# MJE13001_SMPS_5V_1A.net
KiCad netlist of a schematic drawn in Altium Designer
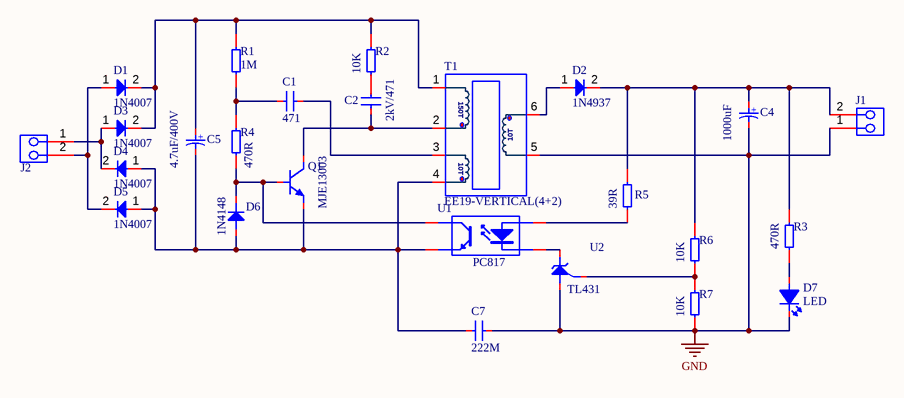
[diagram p0: MJE13001_SMPS_5V_1A.SchDoc]

(export (version "E")
  (design (tool "Eeschema 10.0.6"))
  (components
    (comp (ref "C1")
      (value "471")
      (footprint "CAP_DISC_104")
      (libsource (lib "MyAltiumLibrary") (part "Capacitors(Disc)"))
    )
    (comp (ref "C2")
      (value "2kV/471")
      (footprint "CAP_DISC_Y1222")
      (libsource (lib "MyAltiumLibrary") (part "Capacitors(Disc)"))
    )
    (comp (ref "C4")
      (value "1000uF")
      (footprint "CAP_RAD_D8x11.5_POL_BK")
      (libsource (lib "MyAltiumLibrary") (part "Capacitor(Radian)"))
    )
    (comp (ref "C5")
      (value "4.7uF/400V")
      (footprint "CAP_RAD_D8x11.5_POL_BK")
      (libsource (lib "MyAltiumLibrary") (part "Capacitor(Radian)"))
    )
    (comp (ref "C7")
      (value "222M")
      (footprint "CAP_DISC_Y2222")
      (libsource (lib "MyAltiumLibrary") (part "Capacitors(Disc)"))
    )
    (comp (ref "D1")
      (value "1N4007")
      (footprint "DO-41")
      (libsource (lib "MyAltiumLibrary") (part "Diode-1N4007"))
    )
    (comp (ref "D2")
      (value "1N4937")
      (footprint "DO-41")
      (libsource (lib "MyAltiumLibrary") (part "Diode-1N4937"))
    )
    (comp (ref "D3")
      (value "1N4007")
      (footprint "DO-41")
      (libsource (lib "MyAltiumLibrary") (part "Diode-1N4007"))
    )
    (comp (ref "D4")
      (value "1N4007")
      (footprint "DO-41")
      (libsource (lib "MyAltiumLibrary") (part "Diode-1N4007"))
    )
    (comp (ref "D5")
      (value "1N4007")
      (footprint "DO-41")
      (libsource (lib "MyAltiumLibrary") (part "Diode-1N4007"))
    )
    (comp (ref "D6")
      (value "1N4148")
      (footprint "DO-35 Horizontal")
      (libsource (lib "MyAltiumLibrary") (part "Diode-1N4148"))
    )
    (comp (ref "D7")
      (value "LED")
      (footprint "LED_3MM_GREEN")
      (libsource (lib "MyAltiumLibrary") (part "LED 3MM"))
    )
    (comp (ref "J1")
      (value "DEGSON Screws")
      (footprint "DG127-5.0-02P-14-00AH")
      (libsource (lib "") (part "DG127-5.0-02P-14-00AH_1"))
    )
    (comp (ref "J2")
      (value "DEGSON Screws")
      (footprint "DG127-5.0-02P-14-00AH")
      (libsource (lib "MyAltiumLibrary") (part "DG127-5.0-02P-14-00AH"))
    )
    (comp (ref "Q1")
      (value "MJE13003")
      (footprint "TO-126")
      (libsource (lib "MyAltiumLibrary") (part "Transistor-MJE13003"))
    )
    (comp (ref "R1")
      (value "1M")
      (footprint "RES-0.25W-H-MF")
      (libsource (lib "MyAltiumLibrary") (part "Resistors THD"))
    )
    (comp (ref "R2")
      (value "10K")
      (footprint "RES-0.25W-H-MF")
      (libsource (lib "MyAltiumLibrary") (part "Resistors THD"))
    )
    (comp (ref "R3")
      (value "470R")
      (footprint "RES-0.25W-H-MF")
      (libsource (lib "MyAltiumLibrary") (part "Resistors THD"))
    )
    (comp (ref "R4")
      (value "470R")
      (footprint "RES-0.25W-H-MF")
      (libsource (lib "MyAltiumLibrary") (part "Resistors THD"))
    )
    (comp (ref "R5")
      (value "39R")
      (footprint "RES-0.25W-H-MF")
      (libsource (lib "MyAltiumLibrary") (part "Resistors THD"))
    )
    (comp (ref "R6")
      (value "10K")
      (footprint "RES-0.25W-H-MF")
      (libsource (lib "MyAltiumLibrary") (part "Resistors THD"))
    )
    (comp (ref "R7")
      (value "10K")
      (footprint "RES-0.25W-H-MF")
      (libsource (lib "MyAltiumLibrary") (part "Resistors THD"))
    )
    (comp (ref "T1")
      (value "EE19-VERTICAL(4+2)")
      (footprint "TRANSFORMER-EE19(4+2)")
      (libsource (lib "MyAltiumLibrary") (part "TRANS-EE19-VERTICAL(4+2)"))
    )
    (comp (ref "U1")
      (value "PC817")
      (footprint "PC817-DIP")
      (libsource (lib "MyAltiumLibrary") (part "Opto-PC817"))
    )
    (comp (ref "U2")
      (value "TL431")
      (footprint "TO-92")
      (libsource (lib "MyAltiumLibrary") (part "Ic-TL431"))
    )
  )
  (nets
    (net (code "1") (name "GND") (class "Default")
      (node (ref "C4") (pin "2") (pinfunction "2_2") (pintype "passive"))
      (node (ref "C7") (pin "2") (pinfunction "2_2") (pintype "passive"))
      (node (ref "D7") (pin "2") (pinfunction "K_2") (pintype "passive"))
      (node (ref "J1") (pin "1") (pinfunction "1_1") (pintype "passive"))
      (node (ref "R7") (pin "1") (pinfunction "1_1") (pintype "passive"))
      (node (ref "T1") (pin "5") (pinfunction "5_5") (pintype "passive"))
      (node (ref "U2") (pin "2") (pinfunction "2_2") (pintype "passive"))
    )
    (net (code "2") (name "Net-(C1-Pad1)") (class "Default")
      (node (ref "C1") (pin "1") (pinfunction "1_1") (pintype "passive"))
      (node (ref "R1") (pin "1") (pinfunction "1_1") (pintype "passive"))
      (node (ref "R4") (pin "2") (pinfunction "2_2") (pintype "passive"))
    )
    (net (code "3") (name "Net-(C1-Pad2)") (class "Default")
      (node (ref "C1") (pin "2") (pinfunction "2_2") (pintype "passive"))
      (node (ref "T1") (pin "3") (pinfunction "1_3") (pintype "passive"))
    )
    (net (code "4") (name "Net-(C2-Pad2)") (class "Default")
      (node (ref "C2") (pin "2") (pinfunction "2_2") (pintype "passive"))
      (node (ref "R2") (pin "1") (pinfunction "1_1") (pintype "passive"))
    )
    (net (code "5") (name "Net-(C4-Pad1)") (class "Default")
      (node (ref "C4") (pin "1") (pinfunction "1_1") (pintype "passive"))
      (node (ref "D2") (pin "2") (pinfunction "2_2") (pintype "passive"))
      (node (ref "J1") (pin "2") (pinfunction "2_2") (pintype "passive"))
      (node (ref "R3") (pin "2") (pinfunction "2_2") (pintype "passive"))
      (node (ref "R5") (pin "2") (pinfunction "2_2") (pintype "passive"))
      (node (ref "R6") (pin "2") (pinfunction "2_2") (pintype "passive"))
    )
    (net (code "6") (name "Net-(C5-Pad1)") (class "Default")
      (node (ref "C5") (pin "1") (pinfunction "1_1") (pintype "passive"))
      (node (ref "D1") (pin "2") (pinfunction "2_2") (pintype "passive"))
      (node (ref "D3") (pin "2") (pinfunction "2_2") (pintype "passive"))
      (node (ref "R1") (pin "2") (pinfunction "2_2") (pintype "passive"))
      (node (ref "R2") (pin "2") (pinfunction "2_2") (pintype "passive"))
      (node (ref "T1") (pin "1") (pinfunction "1_1") (pintype "passive"))
    )
    (net (code "7") (name "Net-(D1-Pad1)") (class "Default")
      (node (ref "D1") (pin "1") (pinfunction "1_1") (pintype "passive"))
      (node (ref "D5") (pin "2") (pinfunction "2_2") (pintype "passive"))
      (node (ref "J2") (pin "2") (pinfunction "2_2") (pintype "passive"))
    )
    (net (code "8") (name "Net-(D2-Pad1)") (class "Default")
      (node (ref "D2") (pin "1") (pinfunction "1_1") (pintype "passive"))
      (node (ref "T1") (pin "6") (pinfunction "6_6") (pintype "passive"))
    )
    (net (code "9") (name "Net-(D3-Pad1)") (class "Default")
      (node (ref "D3") (pin "1") (pinfunction "1_1") (pintype "passive"))
      (node (ref "D4") (pin "2") (pinfunction "2_2") (pintype "passive"))
      (node (ref "J2") (pin "1") (pinfunction "1_1") (pintype "passive"))
    )
    (net (code "10") (name "Net-(D7-A)") (class "Default")
      (node (ref "D7") (pin "1") (pinfunction "A_1") (pintype "passive"))
      (node (ref "R3") (pin "1") (pinfunction "1_1") (pintype "passive"))
    )
    (net (code "11") (name "Net-(Q1-B)") (class "Default")
      (node (ref "D6") (pin "2") (pinfunction "2_2") (pintype "passive"))
      (node (ref "Q1") (pin "1") (pinfunction "B_1") (pintype "passive"))
      (node (ref "R4") (pin "1") (pinfunction "1_1") (pintype "passive"))
      (node (ref "U1") (pin "4") (pinfunction "C_4") (pintype "passive"))
    )
    (net (code "12") (name "Net-(Q1-C)") (class "Default")
      (node (ref "C2") (pin "1") (pinfunction "1_1") (pintype "passive"))
      (node (ref "Q1") (pin "2") (pinfunction "C_2") (pintype "passive"))
      (node (ref "T1") (pin "2") (pinfunction "2_2") (pintype "passive"))
    )
    (net (code "13") (name "Net-(Q1-E)") (class "Default")
      (node (ref "C5") (pin "2") (pinfunction "2_2") (pintype "passive"))
      (node (ref "C7") (pin "1") (pinfunction "1_1") (pintype "passive"))
      (node (ref "D4") (pin "1") (pinfunction "1_1") (pintype "passive"))
      (node (ref "D5") (pin "1") (pinfunction "1_1") (pintype "passive"))
      (node (ref "D6") (pin "1") (pinfunction "1_1") (pintype "passive"))
      (node (ref "Q1") (pin "3") (pinfunction "E_3") (pintype "passive"))
      (node (ref "T1") (pin "4") (pinfunction "4_4") (pintype "passive"))
      (node (ref "U1") (pin "3") (pinfunction "E_3") (pintype "passive"))
    )
    (net (code "14") (name "Net-(R6-Pad1)") (class "Default")
      (node (ref "R6") (pin "1") (pinfunction "1_1") (pintype "passive"))
      (node (ref "R7") (pin "2") (pinfunction "2_2") (pintype "passive"))
      (node (ref "U2") (pin "1") (pinfunction "1_1") (pintype "passive"))
    )
    (net (code "15") (name "Net-(U1-A)") (class "Default")
      (node (ref "R5") (pin "1") (pinfunction "1_1") (pintype "passive"))
      (node (ref "U1") (pin "1") (pinfunction "A_1") (pintype "passive"))
    )
    (net (code "16") (name "Net-(U1-K)") (class "Default")
      (node (ref "U1") (pin "2") (pinfunction "K_2") (pintype "passive"))
      (node (ref "U2") (pin "3") (pinfunction "3_3") (pintype "passive"))
    )
  )
)
